# Electromagnetic_Detection_Board.net
KiCad netlist of a schematic drawn in Altium Designer
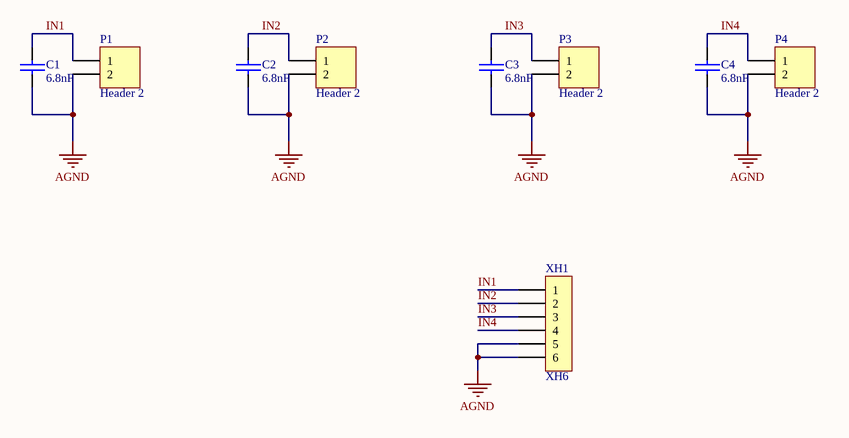
[diagram p0: Electromagnetic Detection Board.SchDoc]

(export (version "E")
  (design (tool "Eeschema 10.0.6"))
  (components
    (comp (ref "C1")
      (value "6.8nF")
      (footprint "0402C")
      (description "无极性电容")
      (libsource (lib "电容") (part "CAP"))
    )
    (comp (ref "C2")
      (value "6.8nF")
      (footprint "0402C")
      (description "无极性电容")
      (libsource (lib "电容") (part "CAP"))
    )
    (comp (ref "C3")
      (value "6.8nF")
      (footprint "0402C")
      (description "无极性电容")
      (libsource (lib "电容") (part "CAP"))
    )
    (comp (ref "C4")
      (value "6.8nF")
      (footprint "0402C")
      (description "无极性电容")
      (libsource (lib "电容") (part "CAP"))
    )
    (comp (ref "P1")
      (value "Header 2")
      (footprint "HDR1X2")
      (description "Header, 2-Pin")
      (fields (field (name "PUBLISHER") "Altium Limited"))
      (libsource (lib "Miscellaneous Connectors") (part "Header 2"))
    )
    (comp (ref "P2")
      (value "Header 2")
      (footprint "HDR1X2")
      (description "Header, 2-Pin")
      (fields (field (name "PUBLISHER") "Altium Limited"))
      (libsource (lib "Miscellaneous Connectors") (part "Header 2"))
    )
    (comp (ref "P3")
      (value "Header 2")
      (footprint "HDR1X2")
      (description "Header, 2-Pin")
      (fields (field (name "PUBLISHER") "Altium Limited"))
      (libsource (lib "Miscellaneous Connectors") (part "Header 2"))
    )
    (comp (ref "P4")
      (value "Header 2")
      (footprint "HDR1X2")
      (description "Header, 2-Pin")
      (fields (field (name "PUBLISHER") "Altium Limited"))
      (libsource (lib "Miscellaneous Connectors") (part "Header 2"))
    )
    (comp (ref "XH1") (value "XH6") (footprint "XH6/2.54mm/180") (libsource (lib "XH，VH") (part "XH6")))
  )
  (nets
    (net (code "1") (name "/IN1") (class "Default")
      (node (ref "C1") (pin "2") (pinfunction "2_2") (pintype "passive"))
      (node (ref "P1") (pin "1") (pinfunction "1_1") (pintype "passive"))
      (node (ref "XH1") (pin "1") (pinfunction "1_1") (pintype "passive"))
    )
    (net (code "2") (name "/IN2") (class "Default")
      (node (ref "C2") (pin "2") (pinfunction "2_2") (pintype "passive"))
      (node (ref "P2") (pin "1") (pinfunction "1_1") (pintype "passive"))
      (node (ref "XH1") (pin "2") (pinfunction "2_2") (pintype "passive"))
    )
    (net (code "3") (name "/IN3") (class "Default")
      (node (ref "C3") (pin "2") (pinfunction "2_2") (pintype "passive"))
      (node (ref "P3") (pin "1") (pinfunction "1_1") (pintype "passive"))
      (node (ref "XH1") (pin "3") (pinfunction "3_3") (pintype "passive"))
    )
    (net (code "4") (name "/IN4") (class "Default")
      (node (ref "C4") (pin "2") (pinfunction "2_2") (pintype "passive"))
      (node (ref "P4") (pin "1") (pinfunction "1_1") (pintype "passive"))
      (node (ref "XH1") (pin "4") (pinfunction "4_4") (pintype "passive"))
    )
    (net (code "5") (name "AGND") (class "Default")
      (node (ref "C1") (pin "1") (pinfunction "1_1") (pintype "passive"))
      (node (ref "C2") (pin "1") (pinfunction "1_1") (pintype "passive"))
      (node (ref "C3") (pin "1") (pinfunction "1_1") (pintype "passive"))
      (node (ref "C4") (pin "1") (pinfunction "1_1") (pintype "passive"))
      (node (ref "P1") (pin "2") (pinfunction "2_2") (pintype "passive"))
      (node (ref "P2") (pin "2") (pinfunction "2_2") (pintype "passive"))
      (node (ref "P3") (pin "2") (pinfunction "2_2") (pintype "passive"))
      (node (ref "P4") (pin "2") (pinfunction "2_2") (pintype "passive"))
      (node (ref "XH1") (pin "5") (pinfunction "5_5") (pintype "passive"))
      (node (ref "XH1") (pin "6") (pinfunction "6_6") (pintype "passive"))
    )
  )
)
